# BV100011_ControlLcd.net
KiCad netlist of a schematic drawn in Altium Designer
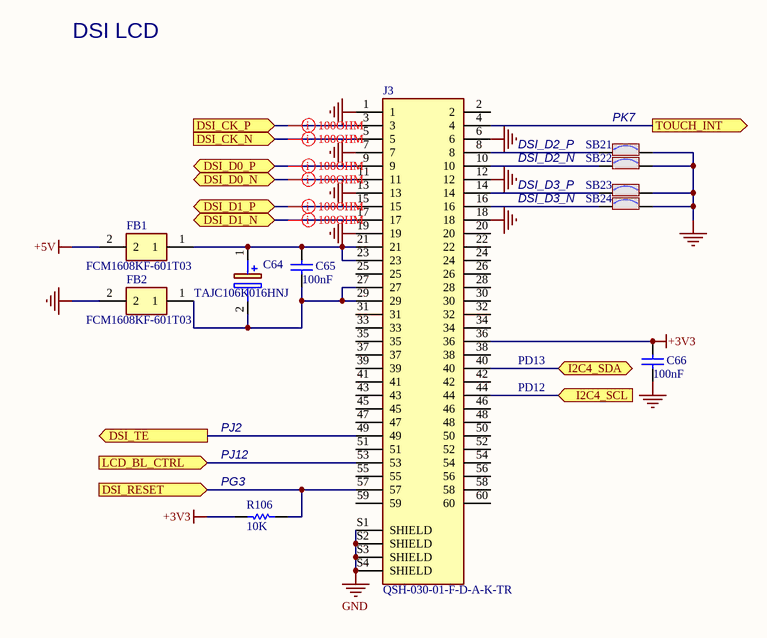
[diagram p0: BV100011_ControlLcd.SchDoc]

(export (version "E")
  (design (tool "Eeschema 10.0.6"))
  (components
    (comp (ref "C64")
      (value "TAJC106K016HNJ")
      (footprint "CAPPM6032X280N")
      (description "Capacitor Polarised")
      (libsource (lib "SamacSys") (part "TAJC106K016HNJ"))
    )
    (comp (ref "C65")
      (value "100nF")
      (footprint "C0603")
      (description "Capacitor")
      (fields (field (name "PUBLISHER") "Altium Limited"))
      (libsource (lib "Miscellaneous Devices") (part "Cap"))
    )
    (comp (ref "C66")
      (value "100nF")
      (footprint "C0603")
      (description "Capacitor")
      (fields (field (name "PUBLISHER") "Altium Limited"))
      (libsource (lib "Miscellaneous Devices") (part "Cap"))
    )
    (comp (ref "FB1")
      (value "FCM1608KF-601T03")
      (footprint "SamacSys:BEADC1608X95N")
      (description "Ferrite Bead")
      (libsource (lib "SamacSys") (part "FCM1608KF-601T03"))
    )
    (comp (ref "FB2")
      (value "FCM1608KF-601T03")
      (footprint "SamacSys:BEADC1608X95N")
      (description "Ferrite Bead")
      (libsource (lib "SamacSys") (part "FCM1608KF-601T03"))
    )
    (comp (ref "J3")
      (value "QSH-030-01-F-D-A-K-TR")
      (footprint "SAMTEC_QSH-030-01-F-D-A-K-TR")
      (description "60 Position Connector Receptacle, Center Strip Contacts Surface Mount Gold")
      (fields (field (name "MF") "Samtec") (field (name "DIGI-KEY_PART_NUMBER") "SAM13214CT-ND"))
      (libsource (lib "QSH-030-01-F-D-A-K-TR") (part "QSH-030-01-F-D-A-K-TR"))
    )
    (comp (ref "R106")
      (value "10K")
      (footprint "R0603")
      (description "Resistor")
      (fields (field (name "PUBLISHER") "Altium Limited"))
      (libsource (lib "Miscellaneous Devices") (part "Res1"))
    )
    (comp (ref "SB21")
      (value "Solder Bridge ON")
      (footprint "SB_0603")
      (libsource (lib "MCD_TOOLS") (part "SB_ON"))
    )
    (comp (ref "SB22")
      (value "Solder Bridge ON")
      (footprint "SB_0603")
      (libsource (lib "MCD_TOOLS") (part "SB_ON"))
    )
    (comp (ref "SB23")
      (value "Solder Bridge ON")
      (footprint "SB_0603")
      (libsource (lib "MCD_TOOLS") (part "SB_ON"))
    )
    (comp (ref "SB24")
      (value "Solder Bridge ON")
      (footprint "SB_0603")
      (libsource (lib "MCD_TOOLS") (part "SB_ON"))
    )
  )
  (nets
    (net (code "1") (name "+3V3") (class "Default")
      (node (ref "C66") (pin "1") (pinfunction "1_1") (pintype "passive"))
      (node (ref "J3") (pin "36") (pinfunction "36_36") (pintype "passive"))
      (node (ref "R106") (pin "2") (pinfunction "2_2") (pintype "passive"))
    )
    (net (code "2") (name "+5V") (class "Default")
      (node (ref "FB1") (pin "2") (pinfunction "2_2") (pintype "passive"))
    )
    (net (code "3") (name "/DSI_CK_N") (class "Default")
      (node (ref "J3") (pin "5") (pinfunction "5_5") (pintype "passive"))
    )
    (net (code "4") (name "/DSI_CK_P") (class "Default")
      (node (ref "J3") (pin "3") (pinfunction "3_3") (pintype "passive"))
    )
    (net (code "5") (name "/DSI_D0_N") (class "Default")
      (node (ref "J3") (pin "11") (pinfunction "11_11") (pintype "passive"))
    )
    (net (code "6") (name "/DSI_D0_P") (class "Default")
      (node (ref "J3") (pin "9") (pinfunction "9_9") (pintype "passive"))
    )
    (net (code "7") (name "/DSI_D1_N") (class "Default")
      (node (ref "J3") (pin "17") (pinfunction "17_17") (pintype "passive"))
    )
    (net (code "8") (name "/DSI_D1_P") (class "Default")
      (node (ref "J3") (pin "15") (pinfunction "15_15") (pintype "passive"))
    )
    (net (code "9") (name "/DSI_RESET") (class "Default")
      (node (ref "J3") (pin "57") (pinfunction "57_57") (pintype "passive"))
      (node (ref "R106") (pin "1") (pinfunction "1_1") (pintype "passive"))
    )
    (net (code "10") (name "/DSI_TE") (class "Default")
      (node (ref "J3") (pin "49") (pinfunction "49_49") (pintype "passive"))
    )
    (net (code "11") (name "/I2C4_SCL") (class "Default")
      (node (ref "J3") (pin "44") (pinfunction "44_44") (pintype "passive"))
    )
    (net (code "12") (name "/I2C4_SDA") (class "Default")
      (node (ref "J3") (pin "40") (pinfunction "40_40") (pintype "passive"))
    )
    (net (code "13") (name "/LCD_BL_CTRL") (class "Default")
      (node (ref "J3") (pin "53") (pinfunction "53_53") (pintype "passive"))
    )
    (net (code "14") (name "/TOUCH_INT") (class "Default")
      (node (ref "J3") (pin "4") (pinfunction "4_4") (pintype "passive"))
    )
    (net (code "15") (name "GND") (class "Default")
      (node (ref "C66") (pin "2") (pinfunction "2_2") (pintype "passive"))
      (node (ref "FB2") (pin "2") (pinfunction "2_2") (pintype "passive"))
      (node (ref "J3") (pin "1") (pinfunction "1_1") (pintype "passive"))
      (node (ref "J3") (pin "12") (pinfunction "12_12") (pintype "passive"))
      (node (ref "J3") (pin "13") (pinfunction "13_13") (pintype "passive"))
      (node (ref "J3") (pin "18") (pinfunction "18_18") (pintype "passive"))
      (node (ref "J3") (pin "19") (pinfunction "19_19") (pintype "passive"))
      (node (ref "J3") (pin "6") (pinfunction "6_6") (pintype "passive"))
      (node (ref "J3") (pin "7") (pinfunction "7_7") (pintype "passive"))
      (node (ref "J3") (pin "S1") (pinfunction "SHIELD_S1") (pintype "passive"))
      (node (ref "J3") (pin "S2") (pinfunction "SHIELD_S2") (pintype "passive"))
      (node (ref "J3") (pin "S3") (pinfunction "SHIELD_S3") (pintype "passive"))
      (node (ref "J3") (pin "S4") (pinfunction "SHIELD_S4") (pintype "passive"))
      (node (ref "SB21") (pin "2") (pinfunction "2_2") (pintype "passive"))
      (node (ref "SB22") (pin "2") (pinfunction "2_2") (pintype "passive"))
      (node (ref "SB23") (pin "2") (pinfunction "2_2") (pintype "passive"))
      (node (ref "SB24") (pin "2") (pinfunction "2_2") (pintype "passive"))
    )
    (net (code "16") (name "Net-(C64-+)") (class "Default")
      (node (ref "C64") (pin "1") (pinfunction "+_1") (pintype "passive"))
      (node (ref "C65") (pin "1") (pinfunction "1_1") (pintype "passive"))
      (node (ref "FB1") (pin "1") (pinfunction "1_1") (pintype "passive"))
      (node (ref "J3") (pin "21") (pinfunction "21_21") (pintype "passive"))
      (node (ref "J3") (pin "23") (pinfunction "23_23") (pintype "passive"))
    )
    (net (code "17") (name "Net-(C64--)") (class "Default")
      (node (ref "C64") (pin "2") (pinfunction "-_2") (pintype "passive"))
      (node (ref "C65") (pin "2") (pinfunction "2_2") (pintype "passive"))
      (node (ref "FB2") (pin "1") (pinfunction "1_1") (pintype "passive"))
      (node (ref "J3") (pin "27") (pinfunction "27_27") (pintype "passive"))
      (node (ref "J3") (pin "29") (pinfunction "29_29") (pintype "passive"))
    )
    (net (code "18") (name "Net-(J3-Pad8)") (class "Default")
      (node (ref "J3") (pin "8") (pinfunction "8_8") (pintype "passive"))
      (node (ref "SB21") (pin "1") (pinfunction "1_1") (pintype "passive"))
    )
    (net (code "19") (name "Net-(J3-Pad10)") (class "Default")
      (node (ref "J3") (pin "10") (pinfunction "10_10") (pintype "passive"))
      (node (ref "SB22") (pin "1") (pinfunction "1_1") (pintype "passive"))
    )
    (net (code "20") (name "Net-(J3-Pad14)") (class "Default")
      (node (ref "J3") (pin "14") (pinfunction "14_14") (pintype "passive"))
      (node (ref "SB23") (pin "1") (pinfunction "1_1") (pintype "passive"))
    )
    (net (code "21") (name "Net-(J3-Pad16)") (class "Default")
      (node (ref "J3") (pin "16") (pinfunction "16_16") (pintype "passive"))
      (node (ref "SB24") (pin "1") (pinfunction "1_1") (pintype "passive"))
    )
    (net (code "22") (name "unconnected-(J3-Pad2)") (class "Default")
      (node (ref "J3") (pin "2") (pinfunction "2_2") (pintype "passive"))
    )
    (net (code "23") (name "unconnected-(J3-Pad20)") (class "Default")
      (node (ref "J3") (pin "20") (pinfunction "20_20") (pintype "passive"))
    )
    (net (code "24") (name "unconnected-(J3-Pad22)") (class "Default")
      (node (ref "J3") (pin "22") (pinfunction "22_22") (pintype "passive"))
    )
    (net (code "25") (name "unconnected-(J3-Pad24)") (class "Default")
      (node (ref "J3") (pin "24") (pinfunction "24_24") (pintype "passive"))
    )
    (net (code "26") (name "unconnected-(J3-Pad25)") (class "Default")
      (node (ref "J3") (pin "25") (pinfunction "25_25") (pintype "passive"))
    )
    (net (code "27") (name "unconnected-(J3-Pad26)") (class "Default")
      (node (ref "J3") (pin "26") (pinfunction "26_26") (pintype "passive"))
    )
    (net (code "28") (name "unconnected-(J3-Pad28)") (class "Default")
      (node (ref "J3") (pin "28") (pinfunction "28_28") (pintype "passive"))
    )
    (net (code "29") (name "unconnected-(J3-Pad30)") (class "Default")
      (node (ref "J3") (pin "30") (pinfunction "30_30") (pintype "passive"))
    )
    (net (code "30") (name "unconnected-(J3-Pad31)") (class "Default")
      (node (ref "J3") (pin "31") (pinfunction "31_31") (pintype "passive"))
    )
    (net (code "31") (name "unconnected-(J3-Pad32)") (class "Default")
      (node (ref "J3") (pin "32") (pinfunction "32_32") (pintype "passive"))
    )
    (net (code "32") (name "unconnected-(J3-Pad33)") (class "Default")
      (node (ref "J3") (pin "33") (pinfunction "33_33") (pintype "passive"))
    )
    (net (code "33") (name "unconnected-(J3-Pad34)") (class "Default")
      (node (ref "J3") (pin "34") (pinfunction "34_34") (pintype "passive"))
    )
    (net (code "34") (name "unconnected-(J3-Pad35)") (class "Default")
      (node (ref "J3") (pin "35") (pinfunction "35_35") (pintype "passive"))
    )
    (net (code "35") (name "unconnected-(J3-Pad37)") (class "Default")
      (node (ref "J3") (pin "37") (pinfunction "37_37") (pintype "passive"))
    )
    (net (code "36") (name "unconnected-(J3-Pad38)") (class "Default")
      (node (ref "J3") (pin "38") (pinfunction "38_38") (pintype "passive"))
    )
    (net (code "37") (name "unconnected-(J3-Pad39)") (class "Default")
      (node (ref "J3") (pin "39") (pinfunction "39_39") (pintype "passive"))
    )
    (net (code "38") (name "unconnected-(J3-Pad41)") (class "Default")
      (node (ref "J3") (pin "41") (pinfunction "41_41") (pintype "passive"))
    )
    (net (code "39") (name "unconnected-(J3-Pad42)") (class "Default")
      (node (ref "J3") (pin "42") (pinfunction "42_42") (pintype "passive"))
    )
    (net (code "40") (name "unconnected-(J3-Pad43)") (class "Default")
      (node (ref "J3") (pin "43") (pinfunction "43_43") (pintype "passive"))
    )
    (net (code "41") (name "unconnected-(J3-Pad45)") (class "Default")
      (node (ref "J3") (pin "45") (pinfunction "45_45") (pintype "passive"))
    )
    (net (code "42") (name "unconnected-(J3-Pad46)") (class "Default")
      (node (ref "J3") (pin "46") (pinfunction "46_46") (pintype "passive"))
    )
    (net (code "43") (name "unconnected-(J3-Pad47)") (class "Default")
      (node (ref "J3") (pin "47") (pinfunction "47_47") (pintype "passive"))
    )
    (net (code "44") (name "unconnected-(J3-Pad48)") (class "Default")
      (node (ref "J3") (pin "48") (pinfunction "48_48") (pintype "passive"))
    )
    (net (code "45") (name "unconnected-(J3-Pad50)") (class "Default")
      (node (ref "J3") (pin "50") (pinfunction "50_50") (pintype "passive"))
    )
    (net (code "46") (name "unconnected-(J3-Pad51)") (class "Default")
      (node (ref "J3") (pin "51") (pinfunction "51_51") (pintype "passive"))
    )
    (net (code "47") (name "unconnected-(J3-Pad52)") (class "Default")
      (node (ref "J3") (pin "52") (pinfunction "52_52") (pintype "passive"))
    )
    (net (code "48") (name "unconnected-(J3-Pad54)") (class "Default")
      (node (ref "J3") (pin "54") (pinfunction "54_54") (pintype "passive"))
    )
    (net (code "49") (name "unconnected-(J3-Pad55)") (class "Default")
      (node (ref "J3") (pin "55") (pinfunction "55_55") (pintype "passive"))
    )
    (net (code "50") (name "unconnected-(J3-Pad56)") (class "Default")
      (node (ref "J3") (pin "56") (pinfunction "56_56") (pintype "passive"))
    )
    (net (code "51") (name "unconnected-(J3-Pad58)") (class "Default")
      (node (ref "J3") (pin "58") (pinfunction "58_58") (pintype "passive"))
    )
    (net (code "52") (name "unconnected-(J3-Pad59)") (class "Default")
      (node (ref "J3") (pin "59") (pinfunction "59_59") (pintype "passive"))
    )
    (net (code "53") (name "unconnected-(J3-Pad60)") (class "Default")
      (node (ref "J3") (pin "60") (pinfunction "60_60") (pintype "passive"))
    )
  )
)
